# Sheet2.net
KiCad netlist of a schematic drawn in Altium Designer
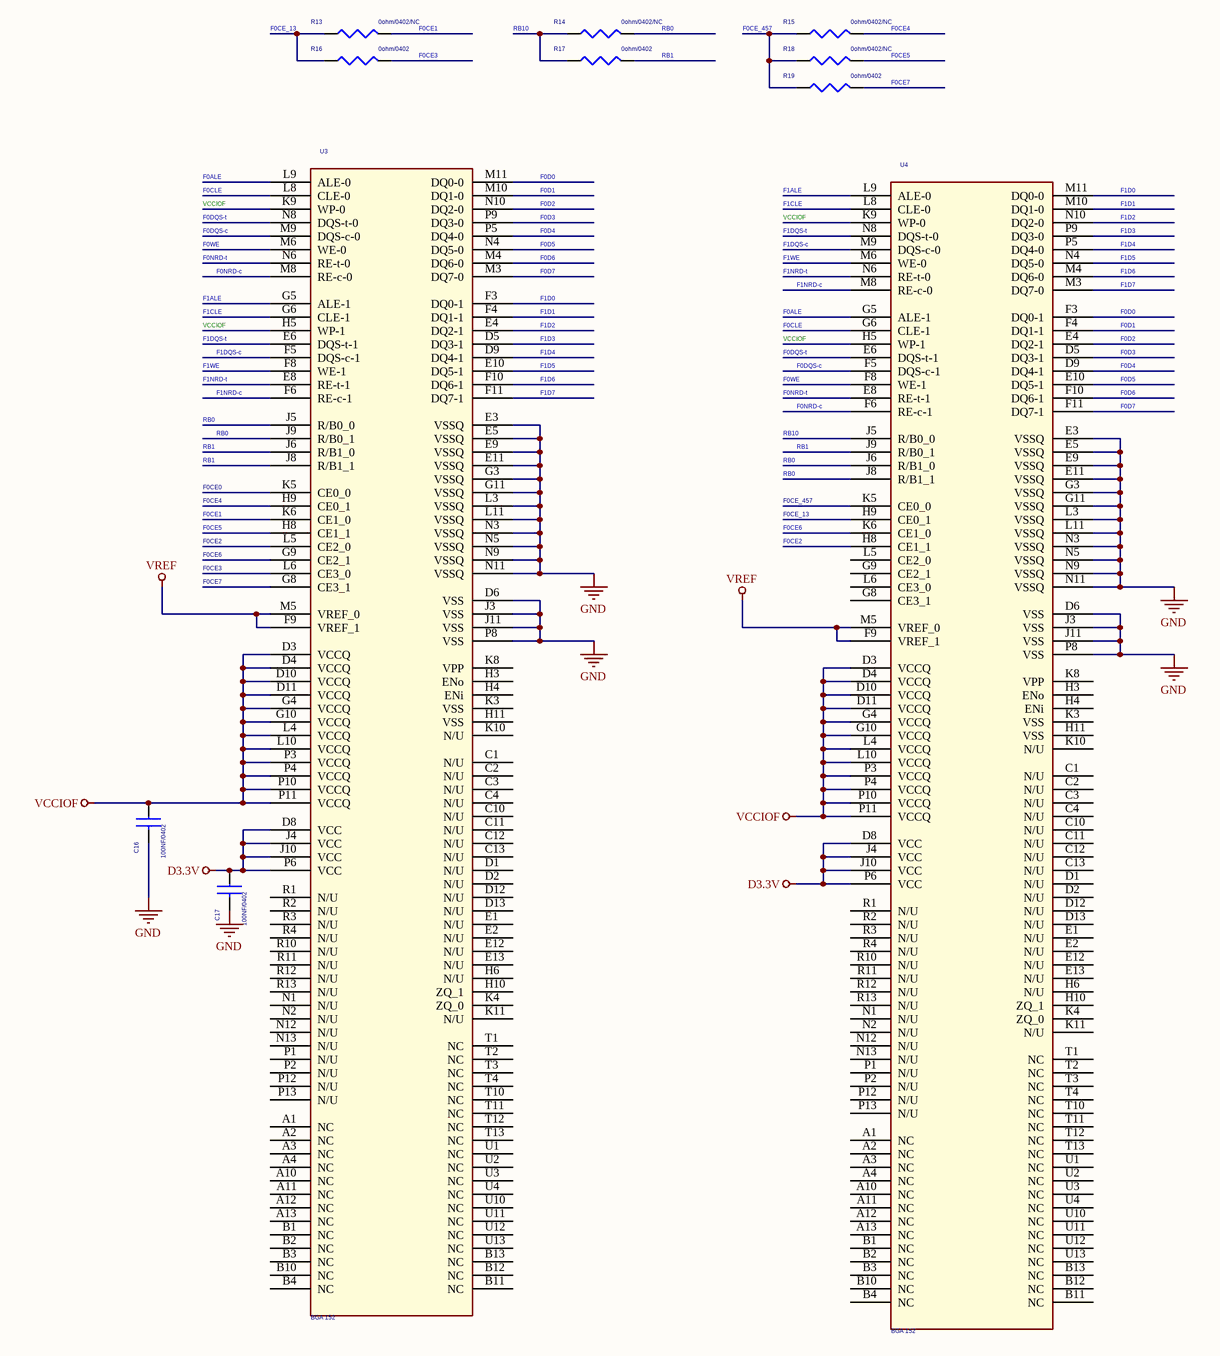
[diagram p0: Sheet2.SchDoc]

(export (version "E")
  (design (tool "Eeschema 10.0.6"))
  (components
    (comp (ref "C16")
      (value "100NF/0402")
      (footprint "C0402")
      (fields
        (field (name "TOLERANCE") "+80/-20%")
        (field (name "PART_NUMBER") "11G101104340")
        (field (name "MANUFACTURER") "WALSIN")
      )
      (libsource (lib "*") (part "C0402_Dup1"))
    )
    (comp (ref "C17")
      (value "100NF/0402")
      (footprint "C0402")
      (fields
        (field (name "TOLERANCE") "+80/-20%")
        (field (name "PART_NUMBER") "11G101104340")
        (field (name "MANUFACTURER") "WALSIN")
      )
      (libsource (lib "*") (part "C0402_Dup1"))
    )
    (comp (ref "R13") (value "0ohm/0402/NC") (footprint "R0201") (libsource (lib "*") (part "R")))
    (comp (ref "R14") (value "0ohm/0402/NC") (footprint "R0201") (libsource (lib "*") (part "R")))
    (comp (ref "R15") (value "0ohm/0402/NC") (footprint "R0201") (libsource (lib "*") (part "R")))
    (comp (ref "R16") (value "0ohm/0402") (footprint "R0201") (libsource (lib "*") (part "R")))
    (comp (ref "R17") (value "0ohm/0402") (footprint "R0201") (libsource (lib "*") (part "R")))
    (comp (ref "R18") (value "0ohm/0402/NC") (footprint "R0201") (libsource (lib "*") (part "R")))
    (comp (ref "R19") (value "0ohm/0402") (footprint "R0201") (libsource (lib "*") (part "R")))
    (comp (ref "U3") (value "BGA 152") (footprint "bga152_1_0_14x18") (libsource (lib "*") (part "TMP_0")))
    (comp (ref "U4") (value "BGA 152") (footprint "bga152_1_0_14x18") (libsource (lib "*") (part "TMP_0")))
  )
  (nets
    (net (code "1") (name "/F0ALE") (class "Default")
      (node (ref "U3") (pin "L9") (pinfunction "ALE-0_L9") (pintype "passive"))
      (node (ref "U4") (pin "G5") (pinfunction "ALE-1_G5") (pintype "passive"))
    )
    (net (code "2") (name "/F0CE0") (class "Default")
      (node (ref "U3") (pin "K5") (pinfunction "CE0_0_K5") (pintype "passive"))
    )
    (net (code "3") (name "/F0CE1") (class "Default")
      (node (ref "R13") (pin "2") (pinfunction "2_2") (pintype "passive"))
      (node (ref "U3") (pin "K6") (pinfunction "CE1_0_K6") (pintype "passive"))
    )
    (net (code "4") (name "/F0CE2") (class "Default")
      (node (ref "U3") (pin "L5") (pinfunction "CE2_0_L5") (pintype "passive"))
      (node (ref "U4") (pin "H8") (pinfunction "CE1_1_H8") (pintype "passive"))
    )
    (net (code "5") (name "/F0CE3") (class "Default")
      (node (ref "R16") (pin "2") (pinfunction "2_2") (pintype "passive"))
      (node (ref "U3") (pin "L6") (pinfunction "CE3_0_L6") (pintype "passive"))
    )
    (net (code "6") (name "/F0CE4") (class "Default")
      (node (ref "R15") (pin "2") (pinfunction "2_2") (pintype "passive"))
      (node (ref "U3") (pin "H9") (pinfunction "CE0_1_H9") (pintype "passive"))
    )
    (net (code "7") (name "/F0CE5") (class "Default")
      (node (ref "R18") (pin "2") (pinfunction "2_2") (pintype "passive"))
      (node (ref "U3") (pin "H8") (pinfunction "CE1_1_H8") (pintype "passive"))
    )
    (net (code "8") (name "/F0CE6") (class "Default")
      (node (ref "U3") (pin "G9") (pinfunction "CE2_1_G9") (pintype "passive"))
      (node (ref "U4") (pin "K6") (pinfunction "CE1_0_K6") (pintype "passive"))
    )
    (net (code "9") (name "/F0CE7") (class "Default")
      (node (ref "R19") (pin "2") (pinfunction "2_2") (pintype "passive"))
      (node (ref "U3") (pin "G8") (pinfunction "CE3_1_G8") (pintype "passive"))
    )
    (net (code "10") (name "/F0CE_13") (class "Default")
      (node (ref "R13") (pin "1") (pinfunction "1_1") (pintype "passive"))
      (node (ref "R16") (pin "1") (pinfunction "1_1") (pintype "passive"))
      (node (ref "U4") (pin "H9") (pinfunction "CE0_1_H9") (pintype "passive"))
    )
    (net (code "11") (name "/F0CE_457") (class "Default")
      (node (ref "R15") (pin "1") (pinfunction "1_1") (pintype "passive"))
      (node (ref "R18") (pin "1") (pinfunction "1_1") (pintype "passive"))
      (node (ref "R19") (pin "1") (pinfunction "1_1") (pintype "passive"))
      (node (ref "U4") (pin "K5") (pinfunction "CE0_0_K5") (pintype "passive"))
    )
    (net (code "12") (name "/F0CLE") (class "Default")
      (node (ref "U3") (pin "L8") (pinfunction "CLE-0_L8") (pintype "passive"))
      (node (ref "U4") (pin "G6") (pinfunction "CLE-1_G6") (pintype "passive"))
    )
    (net (code "13") (name "/F0D0") (class "Default")
      (node (ref "U3") (pin "M11") (pinfunction "DQ0-0_M11") (pintype "passive"))
      (node (ref "U4") (pin "F3") (pinfunction "DQ0-1_F3") (pintype "passive"))
    )
    (net (code "14") (name "/F0D1") (class "Default")
      (node (ref "U3") (pin "M10") (pinfunction "DQ1-0_M10") (pintype "passive"))
      (node (ref "U4") (pin "F4") (pinfunction "DQ1-1_F4") (pintype "passive"))
    )
    (net (code "15") (name "/F0D2") (class "Default")
      (node (ref "U3") (pin "N10") (pinfunction "DQ2-0_N10") (pintype "passive"))
      (node (ref "U4") (pin "E4") (pinfunction "DQ2-1_E4") (pintype "passive"))
    )
    (net (code "16") (name "/F0D3") (class "Default")
      (node (ref "U3") (pin "P9") (pinfunction "DQ3-0_P9") (pintype "passive"))
      (node (ref "U4") (pin "D5") (pinfunction "DQ3-1_D5") (pintype "passive"))
    )
    (net (code "17") (name "/F0D4") (class "Default")
      (node (ref "U3") (pin "P5") (pinfunction "DQ4-0_P5") (pintype "passive"))
      (node (ref "U4") (pin "D9") (pinfunction "DQ4-1_D9") (pintype "passive"))
    )
    (net (code "18") (name "/F0D5") (class "Default")
      (node (ref "U3") (pin "N4") (pinfunction "DQ5-0_N4") (pintype "passive"))
      (node (ref "U4") (pin "E10") (pinfunction "DQ5-1_E10") (pintype "passive"))
    )
    (net (code "19") (name "/F0D6") (class "Default")
      (node (ref "U3") (pin "M4") (pinfunction "DQ6-0_M4") (pintype "passive"))
      (node (ref "U4") (pin "F10") (pinfunction "DQ6-1_F10") (pintype "passive"))
    )
    (net (code "20") (name "/F0D7") (class "Default")
      (node (ref "U3") (pin "M3") (pinfunction "DQ7-0_M3") (pintype "passive"))
      (node (ref "U4") (pin "F11") (pinfunction "DQ7-1_F11") (pintype "passive"))
    )
    (net (code "21") (name "/F0DQS-c") (class "Default")
      (node (ref "U3") (pin "M9") (pinfunction "DQS-c-0_M9") (pintype "passive"))
      (node (ref "U4") (pin "F5") (pinfunction "DQS-c-1_F5") (pintype "passive"))
    )
    (net (code "22") (name "/F0DQS-t") (class "Default")
      (node (ref "U3") (pin "N8") (pinfunction "DQS-t-0_N8") (pintype "passive"))
      (node (ref "U4") (pin "E6") (pinfunction "DQS-t-1_E6") (pintype "passive"))
    )
    (net (code "23") (name "/F0NRD-c") (class "Default")
      (node (ref "U3") (pin "M8") (pinfunction "RE-c-0_M8") (pintype "passive"))
      (node (ref "U4") (pin "F6") (pinfunction "RE-c-1_F6") (pintype "passive"))
    )
    (net (code "24") (name "/F0NRD-t") (class "Default")
      (node (ref "U3") (pin "N6") (pinfunction "RE-t-0_N6") (pintype "passive"))
      (node (ref "U4") (pin "E8") (pinfunction "RE-t-1_E8") (pintype "passive"))
    )
    (net (code "25") (name "/F0WE") (class "Default")
      (node (ref "U3") (pin "M6") (pinfunction "WE-0_M6") (pintype "passive"))
      (node (ref "U4") (pin "F8") (pinfunction "WE-1_F8") (pintype "passive"))
    )
    (net (code "26") (name "/F1ALE") (class "Default")
      (node (ref "U3") (pin "G5") (pinfunction "ALE-1_G5") (pintype "passive"))
      (node (ref "U4") (pin "L9") (pinfunction "ALE-0_L9") (pintype "passive"))
    )
    (net (code "27") (name "/F1CLE") (class "Default")
      (node (ref "U3") (pin "G6") (pinfunction "CLE-1_G6") (pintype "passive"))
      (node (ref "U4") (pin "L8") (pinfunction "CLE-0_L8") (pintype "passive"))
    )
    (net (code "28") (name "/F1D0") (class "Default")
      (node (ref "U3") (pin "F3") (pinfunction "DQ0-1_F3") (pintype "passive"))
      (node (ref "U4") (pin "M11") (pinfunction "DQ0-0_M11") (pintype "passive"))
    )
    (net (code "29") (name "/F1D1") (class "Default")
      (node (ref "U3") (pin "F4") (pinfunction "DQ1-1_F4") (pintype "passive"))
      (node (ref "U4") (pin "M10") (pinfunction "DQ1-0_M10") (pintype "passive"))
    )
    (net (code "30") (name "/F1D2") (class "Default")
      (node (ref "U3") (pin "E4") (pinfunction "DQ2-1_E4") (pintype "passive"))
      (node (ref "U4") (pin "N10") (pinfunction "DQ2-0_N10") (pintype "passive"))
    )
    (net (code "31") (name "/F1D3") (class "Default")
      (node (ref "U3") (pin "D5") (pinfunction "DQ3-1_D5") (pintype "passive"))
      (node (ref "U4") (pin "P9") (pinfunction "DQ3-0_P9") (pintype "passive"))
    )
    (net (code "32") (name "/F1D4") (class "Default")
      (node (ref "U3") (pin "D9") (pinfunction "DQ4-1_D9") (pintype "passive"))
      (node (ref "U4") (pin "P5") (pinfunction "DQ4-0_P5") (pintype "passive"))
    )
    (net (code "33") (name "/F1D5") (class "Default")
      (node (ref "U3") (pin "E10") (pinfunction "DQ5-1_E10") (pintype "passive"))
      (node (ref "U4") (pin "N4") (pinfunction "DQ5-0_N4") (pintype "passive"))
    )
    (net (code "34") (name "/F1D6") (class "Default")
      (node (ref "U3") (pin "F10") (pinfunction "DQ6-1_F10") (pintype "passive"))
      (node (ref "U4") (pin "M4") (pinfunction "DQ6-0_M4") (pintype "passive"))
    )
    (net (code "35") (name "/F1D7") (class "Default")
      (node (ref "U3") (pin "F11") (pinfunction "DQ7-1_F11") (pintype "passive"))
      (node (ref "U4") (pin "M3") (pinfunction "DQ7-0_M3") (pintype "passive"))
    )
    (net (code "36") (name "/F1DQS-c") (class "Default")
      (node (ref "U3") (pin "F5") (pinfunction "DQS-c-1_F5") (pintype "passive"))
      (node (ref "U4") (pin "M9") (pinfunction "DQS-c-0_M9") (pintype "passive"))
    )
    (net (code "37") (name "/F1DQS-t") (class "Default")
      (node (ref "U3") (pin "E6") (pinfunction "DQS-t-1_E6") (pintype "passive"))
      (node (ref "U4") (pin "N8") (pinfunction "DQS-t-0_N8") (pintype "passive"))
    )
    (net (code "38") (name "/F1NRD-c") (class "Default")
      (node (ref "U3") (pin "F6") (pinfunction "RE-c-1_F6") (pintype "passive"))
      (node (ref "U4") (pin "M8") (pinfunction "RE-c-0_M8") (pintype "passive"))
    )
    (net (code "39") (name "/F1NRD-t") (class "Default")
      (node (ref "U3") (pin "E8") (pinfunction "RE-t-1_E8") (pintype "passive"))
      (node (ref "U4") (pin "N6") (pinfunction "RE-t-0_N6") (pintype "passive"))
    )
    (net (code "40") (name "/F1WE") (class "Default")
      (node (ref "U3") (pin "F8") (pinfunction "WE-1_F8") (pintype "passive"))
      (node (ref "U4") (pin "M6") (pinfunction "WE-0_M6") (pintype "passive"))
    )
    (net (code "41") (name "/RB0") (class "Default")
      (node (ref "R14") (pin "2") (pinfunction "2_2") (pintype "passive"))
      (node (ref "U3") (pin "J5") (pinfunction "R/B0_0_J5") (pintype "passive"))
      (node (ref "U3") (pin "J9") (pinfunction "R/B0_1_J9") (pintype "passive"))
      (node (ref "U4") (pin "J6") (pinfunction "R/B1_0_J6") (pintype "passive"))
      (node (ref "U4") (pin "J8") (pinfunction "R/B1_1_J8") (pintype "passive"))
    )
    (net (code "42") (name "/RB1") (class "Default")
      (node (ref "R17") (pin "2") (pinfunction "2_2") (pintype "passive"))
      (node (ref "U3") (pin "J6") (pinfunction "R/B1_0_J6") (pintype "passive"))
      (node (ref "U3") (pin "J8") (pinfunction "R/B1_1_J8") (pintype "passive"))
      (node (ref "U4") (pin "J9") (pinfunction "R/B0_1_J9") (pintype "passive"))
    )
    (net (code "43") (name "/RB10") (class "Default")
      (node (ref "R14") (pin "1") (pinfunction "1_1") (pintype "passive"))
      (node (ref "R17") (pin "1") (pinfunction "1_1") (pintype "passive"))
      (node (ref "U4") (pin "J5") (pinfunction "R/B0_0_J5") (pintype "passive"))
    )
    (net (code "44") (name "D3.3V") (class "Default")
      (node (ref "C17") (pin "1") (pinfunction "1_1") (pintype "passive"))
      (node (ref "U3") (pin "D8") (pinfunction "VCC_D8") (pintype "passive"))
      (node (ref "U3") (pin "J10") (pinfunction "VCC_J10") (pintype "passive"))
      (node (ref "U3") (pin "J4") (pinfunction "VCC_J4") (pintype "passive"))
      (node (ref "U3") (pin "P6") (pinfunction "VCC_P6") (pintype "passive"))
      (node (ref "U4") (pin "D8") (pinfunction "VCC_D8") (pintype "passive"))
      (node (ref "U4") (pin "J10") (pinfunction "VCC_J10") (pintype "passive"))
      (node (ref "U4") (pin "J4") (pinfunction "VCC_J4") (pintype "passive"))
      (node (ref "U4") (pin "P6") (pinfunction "VCC_P6") (pintype "passive"))
    )
    (net (code "45") (name "GND") (class "Default")
      (node (ref "C16") (pin "2") (pinfunction "2_2") (pintype "passive"))
      (node (ref "C17") (pin "2") (pinfunction "2_2") (pintype "passive"))
      (node (ref "U3") (pin "D6") (pinfunction "VSS_D6") (pintype "passive"))
      (node (ref "U3") (pin "E11") (pinfunction "VSSQ_E11") (pintype "passive"))
      (node (ref "U3") (pin "E3") (pinfunction "VSSQ_E3") (pintype "passive"))
      (node (ref "U3") (pin "E5") (pinfunction "VSSQ_E5") (pintype "passive"))
      (node (ref "U3") (pin "E9") (pinfunction "VSSQ_E9") (pintype "passive"))
      (node (ref "U3") (pin "G11") (pinfunction "VSSQ_G11") (pintype "passive"))
      (node (ref "U3") (pin "G3") (pinfunction "VSSQ_G3") (pintype "passive"))
      (node (ref "U3") (pin "J11") (pinfunction "VSS_J11") (pintype "passive"))
      (node (ref "U3") (pin "J3") (pinfunction "VSS_J3") (pintype "passive"))
      (node (ref "U3") (pin "L11") (pinfunction "VSSQ_L11") (pintype "passive"))
      (node (ref "U3") (pin "L3") (pinfunction "VSSQ_L3") (pintype "passive"))
      (node (ref "U3") (pin "N11") (pinfunction "VSSQ_N11") (pintype "passive"))
      (node (ref "U3") (pin "N3") (pinfunction "VSSQ_N3") (pintype "passive"))
      (node (ref "U3") (pin "N5") (pinfunction "VSSQ_N5") (pintype "passive"))
      (node (ref "U3") (pin "N9") (pinfunction "VSSQ_N9") (pintype "passive"))
      (node (ref "U3") (pin "P8") (pinfunction "VSS_P8") (pintype "passive"))
      (node (ref "U4") (pin "D6") (pinfunction "VSS_D6") (pintype "passive"))
      (node (ref "U4") (pin "E11") (pinfunction "VSSQ_E11") (pintype "passive"))
      (node (ref "U4") (pin "E3") (pinfunction "VSSQ_E3") (pintype "passive"))
      (node (ref "U4") (pin "E5") (pinfunction "VSSQ_E5") (pintype "passive"))
      (node (ref "U4") (pin "E9") (pinfunction "VSSQ_E9") (pintype "passive"))
      (node (ref "U4") (pin "G11") (pinfunction "VSSQ_G11") (pintype "passive"))
      (node (ref "U4") (pin "G3") (pinfunction "VSSQ_G3") (pintype "passive"))
      (node (ref "U4") (pin "J11") (pinfunction "VSS_J11") (pintype "passive"))
      (node (ref "U4") (pin "J3") (pinfunction "VSS_J3") (pintype "passive"))
      (node (ref "U4") (pin "L11") (pinfunction "VSSQ_L11") (pintype "passive"))
      (node (ref "U4") (pin "L3") (pinfunction "VSSQ_L3") (pintype "passive"))
      (node (ref "U4") (pin "N11") (pinfunction "VSSQ_N11") (pintype "passive"))
      (node (ref "U4") (pin "N3") (pinfunction "VSSQ_N3") (pintype "passive"))
      (node (ref "U4") (pin "N5") (pinfunction "VSSQ_N5") (pintype "passive"))
      (node (ref "U4") (pin "N9") (pinfunction "VSSQ_N9") (pintype "passive"))
      (node (ref "U4") (pin "P8") (pinfunction "VSS_P8") (pintype "passive"))
    )
    (net (code "46") (name "VCCIOF") (class "Default")
      (node (ref "C16") (pin "1") (pinfunction "1_1") (pintype "passive"))
      (node (ref "U3") (pin "D10") (pinfunction "VCCQ_D10") (pintype "passive"))
      (node (ref "U3") (pin "D11") (pinfunction "VCCQ_D11") (pintype "passive"))
      (node (ref "U3") (pin "D3") (pinfunction "VCCQ_D3") (pintype "passive"))
      (node (ref "U3") (pin "D4") (pinfunction "VCCQ_D4") (pintype "passive"))
      (node (ref "U3") (pin "G10") (pinfunction "VCCQ_G10") (pintype "passive"))
      (node (ref "U3") (pin "G4") (pinfunction "VCCQ_G4") (pintype "passive"))
      (node (ref "U3") (pin "H5") (pinfunction "WP-1_H5") (pintype "passive"))
      (node (ref "U3") (pin "K9") (pinfunction "WP-0_K9") (pintype "passive"))
      (node (ref "U3") (pin "L10") (pinfunction "VCCQ_L10") (pintype "passive"))
      (node (ref "U3") (pin "L4") (pinfunction "VCCQ_L4") (pintype "passive"))
      (node (ref "U3") (pin "P10") (pinfunction "VCCQ_P10") (pintype "passive"))
      (node (ref "U3") (pin "P11") (pinfunction "VCCQ_P11") (pintype "passive"))
      (node (ref "U3") (pin "P3") (pinfunction "VCCQ_P3") (pintype "passive"))
      (node (ref "U3") (pin "P4") (pinfunction "VCCQ_P4") (pintype "passive"))
      (node (ref "U4") (pin "D10") (pinfunction "VCCQ_D10") (pintype "passive"))
      (node (ref "U4") (pin "D11") (pinfunction "VCCQ_D11") (pintype "passive"))
      (node (ref "U4") (pin "D3") (pinfunction "VCCQ_D3") (pintype "passive"))
      (node (ref "U4") (pin "D4") (pinfunction "VCCQ_D4") (pintype "passive"))
      (node (ref "U4") (pin "G10") (pinfunction "VCCQ_G10") (pintype "passive"))
      (node (ref "U4") (pin "G4") (pinfunction "VCCQ_G4") (pintype "passive"))
      (node (ref "U4") (pin "H5") (pinfunction "WP-1_H5") (pintype "passive"))
      (node (ref "U4") (pin "K9") (pinfunction "WP-0_K9") (pintype "passive"))
      (node (ref "U4") (pin "L10") (pinfunction "VCCQ_L10") (pintype "passive"))
      (node (ref "U4") (pin "L4") (pinfunction "VCCQ_L4") (pintype "passive"))
      (node (ref "U4") (pin "P10") (pinfunction "VCCQ_P10") (pintype "passive"))
      (node (ref "U4") (pin "P11") (pinfunction "VCCQ_P11") (pintype "passive"))
      (node (ref "U4") (pin "P3") (pinfunction "VCCQ_P3") (pintype "passive"))
      (node (ref "U4") (pin "P4") (pinfunction "VCCQ_P4") (pintype "passive"))
    )
    (net (code "47") (name "VREF") (class "Default")
      (node (ref "U3") (pin "F9") (pinfunction "VREF_1_F9") (pintype "passive"))
      (node (ref "U3") (pin "M5") (pinfunction "VREF_0_M5") (pintype "passive"))
      (node (ref "U4") (pin "F9") (pinfunction "VREF_1_F9") (pintype "passive"))
      (node (ref "U4") (pin "M5") (pinfunction "VREF_0_M5") (pintype "passive"))
    )
    (net (code "48") (name "unconnected-(U3-ENi-PadH4)") (class "Default")
      (node (ref "U3") (pin "H4") (pinfunction "ENi_H4") (pintype "passive"))
    )
    (net (code "49") (name "unconnected-(U3-ENo-PadH3)") (class "Default")
      (node (ref "U3") (pin "H3") (pinfunction "ENo_H3") (pintype "passive"))
    )
    (net (code "50") (name "unconnected-(U3-NC-PadA1)") (class "Default")
      (node (ref "U3") (pin "A1") (pinfunction "NC_A1") (pintype "passive"))
    )
    (net (code "51") (name "unconnected-(U3-NC-PadA2)") (class "Default")
      (node (ref "U3") (pin "A2") (pinfunction "NC_A2") (pintype "passive"))
    )
    (net (code "52") (name "unconnected-(U3-NC-PadA3)") (class "Default")
      (node (ref "U3") (pin "A3") (pinfunction "NC_A3") (pintype "passive"))
    )
    (net (code "53") (name "unconnected-(U3-NC-PadA4)") (class "Default")
      (node (ref "U3") (pin "A4") (pinfunction "NC_A4") (pintype "passive"))
    )
    (net (code "54") (name "unconnected-(U3-NC-PadA10)") (class "Default")
      (node (ref "U3") (pin "A10") (pinfunction "NC_A10") (pintype "passive"))
    )
    (net (code "55") (name "unconnected-(U3-NC-PadA11)") (class "Default")
      (node (ref "U3") (pin "A11") (pinfunction "NC_A11") (pintype "passive"))
    )
    (net (code "56") (name "unconnected-(U3-NC-PadA12)") (class "Default")
      (node (ref "U3") (pin "A12") (pinfunction "NC_A12") (pintype "passive"))
    )
    (net (code "57") (name "unconnected-(U3-NC-PadA13)") (class "Default")
      (node (ref "U3") (pin "A13") (pinfunction "NC_A13") (pintype "passive"))
    )
    (net (code "58") (name "unconnected-(U3-NC-PadB1)") (class "Default")
      (node (ref "U3") (pin "B1") (pinfunction "NC_B1") (pintype "passive"))
    )
    (net (code "59") (name "unconnected-(U3-NC-PadB2)") (class "Default")
      (node (ref "U3") (pin "B2") (pinfunction "NC_B2") (pintype "passive"))
    )
    (net (code "60") (name "unconnected-(U3-NC-PadB3)") (class "Default")
      (node (ref "U3") (pin "B3") (pinfunction "NC_B3") (pintype "passive"))
    )
    (net (code "61") (name "unconnected-(U3-NC-PadB4)") (class "Default")
      (node (ref "U3") (pin "B4") (pinfunction "NC_B4") (pintype "passive"))
    )
    (net (code "62") (name "unconnected-(U3-NC-PadB10)") (class "Default")
      (node (ref "U3") (pin "B10") (pinfunction "NC_B10") (pintype "passive"))
    )
    (net (code "63") (name "unconnected-(U3-NC-PadB11)") (class "Default")
      (node (ref "U3") (pin "B11") (pinfunction "NC_B11") (pintype "passive"))
    )
    (net (code "64") (name "unconnected-(U3-NC-PadB12)") (class "Default")
      (node (ref "U3") (pin "B12") (pinfunction "NC_B12") (pintype "passive"))
    )
    (net (code "65") (name "unconnected-(U3-NC-PadB13)") (class "Default")
      (node (ref "U3") (pin "B13") (pinfunction "NC_B13") (pintype "passive"))
    )
    (net (code "66") (name "unconnected-(U3-NC-PadT1)") (class "Default")
      (node (ref "U3") (pin "T1") (pinfunction "NC_T1") (pintype "passive"))
    )
    (net (code "67") (name "unconnected-(U3-NC-PadT2)") (class "Default")
      (node (ref "U3") (pin "T2") (pinfunction "NC_T2") (pintype "passive"))
    )
    (net (code "68") (name "unconnected-(U3-NC-PadT3)") (class "Default")
      (node (ref "U3") (pin "T3") (pinfunction "NC_T3") (pintype "passive"))
    )
    (net (code "69") (name "unconnected-(U3-NC-PadT4)") (class "Default")
      (node (ref "U3") (pin "T4") (pinfunction "NC_T4") (pintype "passive"))
    )
    (net (code "70") (name "unconnected-(U3-NC-PadT10)") (class "Default")
      (node (ref "U3") (pin "T10") (pinfunction "NC_T10") (pintype "passive"))
    )
    (net (code "71") (name "unconnected-(U3-NC-PadT11)") (class "Default")
      (node (ref "U3") (pin "T11") (pinfunction "NC_T11") (pintype "passive"))
    )
    (net (code "72") (name "unconnected-(U3-NC-PadT12)") (class "Default")
      (node (ref "U3") (pin "T12") (pinfunction "NC_T12") (pintype "passive"))
    )
    (net (code "73") (name "unconnected-(U3-NC-PadT13)") (class "Default")
      (node (ref "U3") (pin "T13") (pinfunction "NC_T13") (pintype "passive"))
    )
    (net (code "74") (name "unconnected-(U3-NC-PadU1)") (class "Default")
      (node (ref "U3") (pin "U1") (pinfunction "NC_U1") (pintype "passive"))
    )
    (net (code "75") (name "unconnected-(U3-NC-PadU2)") (class "Default")
      (node (ref "U3") (pin "U2") (pinfunction "NC_U2") (pintype "passive"))
    )
    (net (code "76") (name "unconnected-(U3-NC-PadU3)") (class "Default")
      (node (ref "U3") (pin "U3") (pinfunction "NC_U3") (pintype "passive"))
    )
    (net (code "77") (name "unconnected-(U3-NC-PadU4)") (class "Default")
      (node (ref "U3") (pin "U4") (pinfunction "NC_U4") (pintype "passive"))
    )
    (net (code "78") (name "unconnected-(U3-NC-PadU10)") (class "Default")
      (node (ref "U3") (pin "U10") (pinfunction "NC_U10") (pintype "passive"))
    )
    (net (code "79") (name "unconnected-(U3-NC-PadU11)") (class "Default")
      (node (ref "U3") (pin "U11") (pinfunction "NC_U11") (pintype "passive"))
    )
    (net (code "80") (name "unconnected-(U3-NC-PadU12)") (class "Default")
      (node (ref "U3") (pin "U12") (pinfunction "NC_U12") (pintype "passive"))
    )
    (net (code "81") (name "unconnected-(U3-NC-PadU13)") (class "Default")
      (node (ref "U3") (pin "U13") (pinfunction "NC_U13") (pintype "passive"))
    )
    (net (code "82") (name "unconnected-(U3-N{slash}U-PadC1)") (class "Default")
      (node (ref "U3") (pin "C1") (pinfunction "N/U_C1") (pintype "passive"))
    )
    (net (code "83") (name "unconnected-(U3-N{slash}U-PadC2)") (class "Default")
      (node (ref "U3") (pin "C2") (pinfunction "N/U_C2") (pintype "passive"))
    )
    (net (code "84") (name "unconnected-(U3-N{slash}U-PadC3)") (class "Default")
      (node (ref "U3") (pin "C3") (pinfunction "N/U_C3") (pintype "passive"))
    )
    (net (code "85") (name "unconnected-(U3-N{slash}U-PadC4)") (class "Default")
      (node (ref "U3") (pin "C4") (pinfunction "N/U_C4") (pintype "passive"))
    )
    (net (code "86") (name "unconnected-(U3-N{slash}U-PadC10)") (class "Default")
      (node (ref "U3") (pin "C10") (pinfunction "N/U_C10") (pintype "passive"))
    )
    (net (code "87") (name "unconnected-(U3-N{slash}U-PadC11)") (class "Default")
      (node (ref "U3") (pin "C11") (pinfunction "N/U_C11") (pintype "passive"))
    )
    (net (code "88") (name "unconnected-(U3-N{slash}U-PadC12)") (class "Default")
      (node (ref "U3") (pin "C12") (pinfunction "N/U_C12") (pintype "passive"))
    )
    (net (code "89") (name "unconnected-(U3-N{slash}U-PadC13)") (class "Default")
      (node (ref "U3") (pin "C13") (pinfunction "N/U_C13") (pintype "passive"))
    )
    (net (code "90") (name "unconnected-(U3-N{slash}U-PadD1)") (class "Default")
      (node (ref "U3") (pin "D1") (pinfunction "N/U_D1") (pintype "passive"))
    )
    (net (code "91") (name "unconnected-(U3-N{slash}U-PadD2)") (class "Default")
      (node (ref "U3") (pin "D2") (pinfunction "N/U_D2") (pintype "passive"))
    )
    (net (code "92") (name "unconnected-(U3-N{slash}U-PadD12)") (class "Default")
      (node (ref "U3") (pin "D12") (pinfunction "N/U_D12") (pintype "passive"))
    )
    (net (code "93") (name "unconnected-(U3-N{slash}U-PadD13)") (class "Default")
      (node (ref "U3") (pin "D13") (pinfunction "N/U_D13") (pintype "passive"))
    )
    (net (code "94") (name "unconnected-(U3-N{slash}U-PadE1)") (class "Default")
      (node (ref "U3") (pin "E1") (pinfunction "N/U_E1") (pintype "passive"))
    )
    (net (code "95") (name "unconnected-(U3-N{slash}U-PadE2)") (class "Default")
      (node (ref "U3") (pin "E2") (pinfunction "N/U_E2") (pintype "passive"))
    )
    (net (code "96") (name "unconnected-(U3-N{slash}U-PadE12)") (class "Default")
      (node (ref "U3") (pin "E12") (pinfunction "N/U_E12") (pintype "passive"))
    )
    (net (code "97") (name "unconnected-(U3-N{slash}U-PadE13)") (class "Default")
      (node (ref "U3") (pin "E13") (pinfunction "N/U_E13") (pintype "passive"))
    )
    (net (code "98") (name "unconnected-(U3-N{slash}U-PadH6)") (class "Default")
      (node (ref "U3") (pin "H6") (pinfunction "N/U_H6") (pintype "passive"))
    )
    (net (code "99") (name "unconnected-(U3-N{slash}U-PadK10)") (class "Default")
      (node (ref "U3") (pin "K10") (pinfunction "N/U_K10") (pintype "passive"))
    )
    (net (code "100") (name "unconnected-(U3-N{slash}U-PadK11)") (class "Default")
      (node (ref "U3") (pin "K11") (pinfunction "N/U_K11") (pintype "passive"))
    )
    (net (code "101") (name "unconnected-(U3-N{slash}U-PadN1)") (class "Default")
      (node (ref "U3") (pin "N1") (pinfunction "N/U_N1") (pintype "passive"))
    )
    (net (code "102") (name "unconnected-(U3-N{slash}U-PadN2)") (class "Default")
      (node (ref "U3") (pin "N2") (pinfunction "N/U_N2") (pintype "passive"))
    )
    (net (code "103") (name "unconnected-(U3-N{slash}U-PadN12)") (class "Default")
      (node (ref "U3") (pin "N12") (pinfunction "N/U_N12") (pintype "passive"))
    )
    (net (code "104") (name "unconnected-(U3-N{slash}U-PadN13)") (class "Default")
      (node (ref "U3") (pin "N13") (pinfunction "N/U_N13") (pintype "passive"))
    )
    (net (code "105") (name "unconnected-(U3-N{slash}U-PadP1)") (class "Default")
      (node (ref "U3") (pin "P1") (pinfunction "N/U_P1") (pintype "passive"))
    )
    (net (code "106") (name "unconnected-(U3-N{slash}U-PadP2)") (class "Default")
      (node (ref "U3") (pin "P2") (pinfunction "N/U_P2") (pintype "passive"))
    )
    (net (code "107") (name "unconnected-(U3-N{slash}U-PadP12)") (class "Default")
      (node (ref "U3") (pin "P12") (pinfunction "N/U_P12") (pintype "passive"))
    )
    (net (code "108") (name "unconnected-(U3-N{slash}U-PadP13)") (class "Default")
      (node (ref "U3") (pin "P13") (pinfunction "N/U_P13") (pintype "passive"))
    )
    (net (code "109") (name "unconnected-(U3-N{slash}U-PadR1)") (class "Default")
      (node (ref "U3") (pin "R1") (pinfunction "N/U_R1") (pintype "passive"))
    )
    (net (code "110") (name "unconnected-(U3-N{slash}U-PadR2)") (class "Default")
      (node (ref "U3") (pin "R2") (pinfunction "N/U_R2") (pintype "passive"))
    )
    (net (code "111") (name "unconnected-(U3-N{slash}U-PadR3)") (class "Default")
      (node (ref "U3") (pin "R3") (pinfunction "N/U_R3") (pintype "passive"))
    )
    (net (code "112") (name "unconnected-(U3-N{slash}U-PadR4)") (class "Default")
      (node (ref "U3") (pin "R4") (pinfunction "N/U_R4") (pintype "passive"))
    )
    (net (code "113") (name "unconnected-(U3-N{slash}U-PadR10)") (class "Default")
      (node (ref "U3") (pin "R10") (pinfunction "N/U_R10") (pintype "passive"))
    )
    (net (code "114") (name "unconnected-(U3-N{slash}U-PadR11)") (class "Default")
      (node (ref "U3") (pin "R11") (pinfunction "N/U_R11") (pintype "passive"))
    )
    (net (code "115") (name "unconnected-(U3-N{slash}U-PadR12)") (class "Default")
      (node (ref "U3") (pin "R12") (pinfunction "N/U_R12") (pintype "passive"))
    )
    (net (code "116") (name "unconnected-(U3-N{slash}U-PadR13)") (class "Default")
      (node (ref "U3") (pin "R13") (pinfunction "N/U_R13") (pintype "passive"))
    )
    (net (code "117") (name "unconnected-(U3-VPP-PadK8)") (class "Default")
      (node (ref "U3") (pin "K8") (pinfunction "VPP_K8") (pintype "passive"))
    )
    (net (code "118") (name "unconnected-(U3-VSS-PadH11)") (class "Default")
      (node (ref "U3") (pin "H11") (pinfunction "VSS_H11") (pintype "passive"))
    )
    (net (code "119") (name "unconnected-(U3-VSS-PadK3)") (class "Default")
      (node (ref "U3") (pin "K3") (pinfunction "VSS_K3") (pintype "passive"))
    )
    (net (code "120") (name "unconnected-(U3-ZQ_0-PadK4)") (class "Default")
      (node (ref "U3") (pin "K4") (pinfunction "ZQ_0_K4") (pintype "passive"))
    )
    (net (code "121") (name "unconnected-(U3-ZQ_1-PadH10)") (class "Default")
      (node (ref "U3") (pin "H10") (pinfunction "ZQ_1_H10") (pintype "passive"))
    )
    (net (code "122") (name "unconnected-(U4-CE2_0-PadL5)") (class "Default")
      (node (ref "U4") (pin "L5") (pinfunction "CE2_0_L5") (pintype "passive"))
    )
    (net (code "123") (name "unconnected-(U4-CE2_1-PadG9)") (class "Default")
      (node (ref "U4") (pin "G9") (pinfunction "CE2_1_G9") (pintype "passive"))
    )
    (net (code "124") (name "unconnected-(U4-CE3_0-PadL6)") (class "Default")
      (node (ref "U4") (pin "L6") (pinfunction "CE3_0_L6") (pintype "passive"))
    )
    (net (code "125") (name "unconnected-(U4-CE3_1-PadG8)") (class "Default")
      (node (ref "U4") (pin "G8") (pinfunction "CE3_1_G8") (pintype "passive"))
    )
    (net (code "126") (name "unconnected-(U4-ENi-PadH4)") (class "Default")
      (node (ref "U4") (pin "H4") (pinfunction "ENi_H4") (pintype "passive"))
    )
    (net (code "127") (name "unconnected-(U4-ENo-PadH3)") (class "Default")
      (node (ref "U4") (pin "H3") (pinfunction "ENo_H3") (pintype "passive"))
    )
    (net (code "128") (name "unconnected-(U4-NC-PadA1)") (class "Default")
      (node (ref "U4") (pin "A1") (pinfunction "NC_A1") (pintype "passive"))
    )
    (net (code "129") (name "unconnected-(U4-NC-PadA2)") (class "Default")
      (node (ref "U4") (pin "A2") (pinfunction "NC_A2") (pintype "passive"))
    )
    (net (code "130") (name "unconnected-(U4-NC-PadA3)") (class "Default")
      (node (ref "U4") (pin "A3") (pinfunction "NC_A3") (pintype "passive"))
    )
    (net (code "131") (name "unconnected-(U4-NC-PadA4)") (class "Default")
      (node (ref "U4") (pin "A4") (pinfunction "NC_A4") (pintype "passive"))
    )
    (net (code "132") (name "unconnected-(U4-NC-PadA10)") (class "Default")
      (node (ref "U4") (pin "A10") (pinfunction "NC_A10") (pintype "passive"))
    )
    (net (code "133") (name "unconnected-(U4-NC-PadA11)") (class "Default")
      (node (ref "U4") (pin "A11") (pinfunction "NC_A11") (pintype "passive"))
    )
    (net (code "134") (name "unconnected-(U4-NC-PadA12)") (class "Default")
      (node (ref "U4") (pin "A12") (pinfunction "NC_A12") (pintype "passive"))
    )
    (net (code "135") (name "unconnected-(U4-NC-PadA13)") (class "Default")
      (node (ref "U4") (pin "A13") (pinfunction "NC_A13") (pintype "passive"))
    )
    (net (code "136") (name "unconnected-(U4-NC-PadB1)") (class "Default")
      (node (ref "U4") (pin "B1") (pinfunction "NC_B1") (pintype "passive"))
    )
    (net (code "137") (name "unconnected-(U4-NC-PadB2)") (class "Default")
      (node (ref "U4") (pin "B2") (pinfunction "NC_B2") (pintype "passive"))
    )
    (net (code "138") (name "unconnected-(U4-NC-PadB3)") (class "Default")
      (node (ref "U4") (pin "B3") (pinfunction "NC_B3") (pintype "passive"))
    )
    (net (code "139") (name "unconnected-(U4-NC-PadB4)") (class "Default")
      (node (ref "U4") (pin "B4") (pinfunction "NC_B4") (pintype "passive"))
    )
    (net (code "140") (name "unconnected-(U4-NC-PadB10)") (class "Default")
      (node (ref "U4") (pin "B10") (pinfunction "NC_B10") (pintype "passive"))
    )
    (net (code "141") (name "unconnected-(U4-NC-PadB11)") (class "Default")
      (node (ref "U4") (pin "B11") (pinfunction "NC_B11") (pintype "passive"))
    )
    (net (code "142") (name "unconnected-(U4-NC-PadB12)") (class "Default")
      (node (ref "U4") (pin "B12") (pinfunction "NC_B12") (pintype "passive"))
    )
    (net (code "143") (name "unconnected-(U4-NC-PadB13)") (class "Default")
      (node (ref "U4") (pin "B13") (pinfunction "NC_B13") (pintype "passive"))
    )
    (net (code "144") (name "unconnected-(U4-NC-PadT1)") (class "Default")
      (node (ref "U4") (pin "T1") (pinfunction "NC_T1") (pintype "passive"))
    )
    (net (code "145") (name "unconnected-(U4-NC-PadT2)") (class "Default")
      (node (ref "U4") (pin "T2") (pinfunction "NC_T2") (pintype "passive"))
    )
    (net (code "146") (name "unconnected-(U4-NC-PadT3)") (class "Default")
      (node (ref "U4") (pin "T3") (pinfunction "NC_T3") (pintype "passive"))
    )
    (net (code "147") (name "unconnected-(U4-NC-PadT4)") (class "Default")
      (node (ref "U4") (pin "T4") (pinfunction "NC_T4") (pintype "passive"))
    )
    (net (code "148") (name "unconnected-(U4-NC-PadT10)") (class "Default")
      (node (ref "U4") (pin "T10") (pinfunction "NC_T10") (pintype "passive"))
    )
    (net (code "149") (name "unconnected-(U4-NC-PadT11)") (class "Default")
      (node (ref "U4") (pin "T11") (pinfunction "NC_T11") (pintype "passive"))
    )
    (net (code "150") (name "unconnected-(U4-NC-PadT12)") (class "Default")
      (node (ref "U4") (pin "T12") (pinfunction "NC_T12") (pintype "passive"))
    )
    (net (code "151") (name "unconnected-(U4-NC-PadT13)") (class "Default")
      (node (ref "U4") (pin "T13") (pinfunction "NC_T13") (pintype "passive"))
    )
    (net (code "152") (name "unconnected-(U4-NC-PadU1)") (class "Default")
      (node (ref "U4") (pin "U1") (pinfunction "NC_U1") (pintype "passive"))
    )
    (net (code "153") (name "unconnected-(U4-NC-PadU2)") (class "Default")
      (node (ref "U4") (pin "U2") (pinfunction "NC_U2") (pintype "passive"))
    )
    (net (code "154") (name "unconnected-(U4-NC-PadU3)") (class "Default")
      (node (ref "U4") (pin "U3") (pinfunction "NC_U3") (pintype "passive"))
    )
    (net (code "155") (name "unconnected-(U4-NC-PadU4)") (class "Default")
      (node (ref "U4") (pin "U4") (pinfunction "NC_U4") (pintype "passive"))
    )
    (net (code "156") (name "unconnected-(U4-NC-PadU10)") (class "Default")
      (node (ref "U4") (pin "U10") (pinfunction "NC_U10") (pintype "passive"))
    )
    (net (code "157") (name "unconnected-(U4-NC-PadU11)") (class "Default")
      (node (ref "U4") (pin "U11") (pinfunction "NC_U11") (pintype "passive"))
    )
    (net (code "158") (name "unconnected-(U4-NC-PadU12)") (class "Default")
      (node (ref "U4") (pin "U12") (pinfunction "NC_U12") (pintype "passive"))
    )
    (net (code "159") (name "unconnected-(U4-NC-PadU13)") (class "Default")
      (node (ref "U4") (pin "U13") (pinfunction "NC_U13") (pintype "passive"))
    )
    (net (code "160") (name "unconnected-(U4-N{slash}U-PadC1)") (class "Default")
      (node (ref "U4") (pin "C1") (pinfunction "N/U_C1") (pintype "passive"))
    )
    (net (code "161") (name "unconnected-(U4-N{slash}U-PadC2)") (class "Default")
      (node (ref "U4") (pin "C2") (pinfunction "N/U_C2") (pintype "passive"))
    )
    (net (code "162") (name "unconnected-(U4-N{slash}U-PadC3)") (class "Default")
      (node (ref "U4") (pin "C3") (pinfunction "N/U_C3") (pintype "passive"))
    )
    (net (code "163") (name "unconnected-(U4-N{slash}U-PadC4)") (class "Default")
      (node (ref "U4") (pin "C4") (pinfunction "N/U_C4") (pintype "passive"))
    )
    (net (code "164") (name "unconnected-(U4-N{slash}U-PadC10)") (class "Default")
      (node (ref "U4") (pin "C10") (pinfunction "N/U_C10") (pintype "passive"))
    )
    (net (code "165") (name "unconnected-(U4-N{slash}U-PadC11)") (class "Default")
      (node (ref "U4") (pin "C11") (pinfunction "N/U_C11") (pintype "passive"))
    )
    (net (code "166") (name "unconnected-(U4-N{slash}U-PadC12)") (class "Default")
      (node (ref "U4") (pin "C12") (pinfunction "N/U_C12") (pintype "passive"))
    )
    (net (code "167") (name "unconnected-(U4-N{slash}U-PadC13)") (class "Default")
      (node (ref "U4") (pin "C13") (pinfunction "N/U_C13") (pintype "passive"))
    )
    (net (code "168") (name "unconnected-(U4-N{slash}U-PadD1)") (class "Default")
      (node (ref "U4") (pin "D1") (pinfunction "N/U_D1") (pintype "passive"))
    )
    (net (code "169") (name "unconnected-(U4-N{slash}U-PadD2)") (class "Default")
      (node (ref "U4") (pin "D2") (pinfunction "N/U_D2") (pintype "passive"))
    )
    (net (code "170") (name "unconnected-(U4-N{slash}U-PadD12)") (class "Default")
      (node (ref "U4") (pin "D12") (pinfunction "N/U_D12") (pintype "passive"))
    )
    (net (code "171") (name "unconnected-(U4-N{slash}U-PadD13)") (class "Default")
      (node (ref "U4") (pin "D13") (pinfunction "N/U_D13") (pintype "passive"))
    )
    (net (code "172") (name "unconnected-(U4-N{slash}U-PadE1)") (class "Default")
      (node (ref "U4") (pin "E1") (pinfunction "N/U_E1") (pintype "passive"))
    )
    (net (code "173") (name "unconnected-(U4-N{slash}U-PadE2)") (class "Default")
      (node (ref "U4") (pin "E2") (pinfunction "N/U_E2") (pintype "passive"))
    )
    (net (code "174") (name "unconnected-(U4-N{slash}U-PadE12)") (class "Default")
      (node (ref "U4") (pin "E12") (pinfunction "N/U_E12") (pintype "passive"))
    )
    (net (code "175") (name "unconnected-(U4-N{slash}U-PadE13)") (class "Default")
      (node (ref "U4") (pin "E13") (pinfunction "N/U_E13") (pintype "passive"))
    )
    (net (code "176") (name "unconnected-(U4-N{slash}U-PadH6)") (class "Default")
      (node (ref "U4") (pin "H6") (pinfunction "N/U_H6") (pintype "passive"))
    )
    (net (code "177") (name "unconnected-(U4-N{slash}U-PadK10)") (class "Default")
      (node (ref "U4") (pin "K10") (pinfunction "N/U_K10") (pintype "passive"))
    )
    (net (code "178") (name "unconnected-(U4-N{slash}U-PadK11)") (class "Default")
      (node (ref "U4") (pin "K11") (pinfunction "N/U_K11") (pintype "passive"))
    )
    (net (code "179") (name "unconnected-(U4-N{slash}U-PadN1)") (class "Default")
      (node (ref "U4") (pin "N1") (pinfunction "N/U_N1") (pintype "passive"))
    )
    (net (code "180") (name "unconnected-(U4-N{slash}U-PadN2)") (class "Default")
      (node (ref "U4") (pin "N2") (pinfunction "N/U_N2") (pintype "passive"))
    )
    (net (code "181") (name "unconnected-(U4-N{slash}U-PadN12)") (class "Default")
      (node (ref "U4") (pin "N12") (pinfunction "N/U_N12") (pintype "passive"))
    )
    (net (code "182") (name "unconnected-(U4-N{slash}U-PadN13)") (class "Default")
      (node (ref "U4") (pin "N13") (pinfunction "N/U_N13") (pintype "passive"))
    )
    (net (code "183") (name "unconnected-(U4-N{slash}U-PadP1)") (class "Default")
      (node (ref "U4") (pin "P1") (pinfunction "N/U_P1") (pintype "passive"))
    )
    (net (code "184") (name "unconnected-(U4-N{slash}U-PadP2)") (class "Default")
      (node (ref "U4") (pin "P2") (pinfunction "N/U_P2") (pintype "passive"))
    )
    (net (code "185") (name "unconnected-(U4-N{slash}U-PadP12)") (class "Default")
      (node (ref "U4") (pin "P12") (pinfunction "N/U_P12") (pintype "passive"))
    )
    (net (code "186") (name "unconnected-(U4-N{slash}U-PadP13)") (class "Default")
      (node (ref "U4") (pin "P13") (pinfunction "N/U_P13") (pintype "passive"))
    )
    (net (code "187") (name "unconnected-(U4-N{slash}U-PadR1)") (class "Default")
      (node (ref "U4") (pin "R1") (pinfunction "N/U_R1") (pintype "passive"))
    )
    (net (code "188") (name "unconnected-(U4-N{slash}U-PadR2)") (class "Default")
      (node (ref "U4") (pin "R2") (pinfunction "N/U_R2") (pintype "passive"))
    )
    (net (code "189") (name "unconnected-(U4-N{slash}U-PadR3)") (class "Default")
      (node (ref "U4") (pin "R3") (pinfunction "N/U_R3") (pintype "passive"))
    )
    (net (code "190") (name "unconnected-(U4-N{slash}U-PadR4)") (class "Default")
      (node (ref "U4") (pin "R4") (pinfunction "N/U_R4") (pintype "passive"))
    )
    (net (code "191") (name "unconnected-(U4-N{slash}U-PadR10)") (class "Default")
      (node (ref "U4") (pin "R10") (pinfunction "N/U_R10") (pintype "passive"))
    )
    (net (code "192") (name "unconnected-(U4-N{slash}U-PadR11)") (class "Default")
      (node (ref "U4") (pin "R11") (pinfunction "N/U_R11") (pintype "passive"))
    )
    (net (code "193") (name "unconnected-(U4-N{slash}U-PadR12)") (class "Default")
      (node (ref "U4") (pin "R12") (pinfunction "N/U_R12") (pintype "passive"))
    )
    (net (code "194") (name "unconnected-(U4-N{slash}U-PadR13)") (class "Default")
      (node (ref "U4") (pin "R13") (pinfunction "N/U_R13") (pintype "passive"))
    )
    (net (code "195") (name "unconnected-(U4-VPP-PadK8)") (class "Default")
      (node (ref "U4") (pin "K8") (pinfunction "VPP_K8") (pintype "passive"))
    )
    (net (code "196") (name "unconnected-(U4-VSS-PadH11)") (class "Default")
      (node (ref "U4") (pin "H11") (pinfunction "VSS_H11") (pintype "passive"))
    )
    (net (code "197") (name "unconnected-(U4-VSS-PadK3)") (class "Default")
      (node (ref "U4") (pin "K3") (pinfunction "VSS_K3") (pintype "passive"))
    )
    (net (code "198") (name "unconnected-(U4-ZQ_0-PadK4)") (class "Default")
      (node (ref "U4") (pin "K4") (pinfunction "ZQ_0_K4") (pintype "passive"))
    )
    (net (code "199") (name "unconnected-(U4-ZQ_1-PadH10)") (class "Default")
      (node (ref "U4") (pin "H10") (pinfunction "ZQ_1_H10") (pintype "passive"))
    )
  )
)
